# BaseMachine_Exio_Board.net
KiCad netlist of a schematic drawn in EAGLE
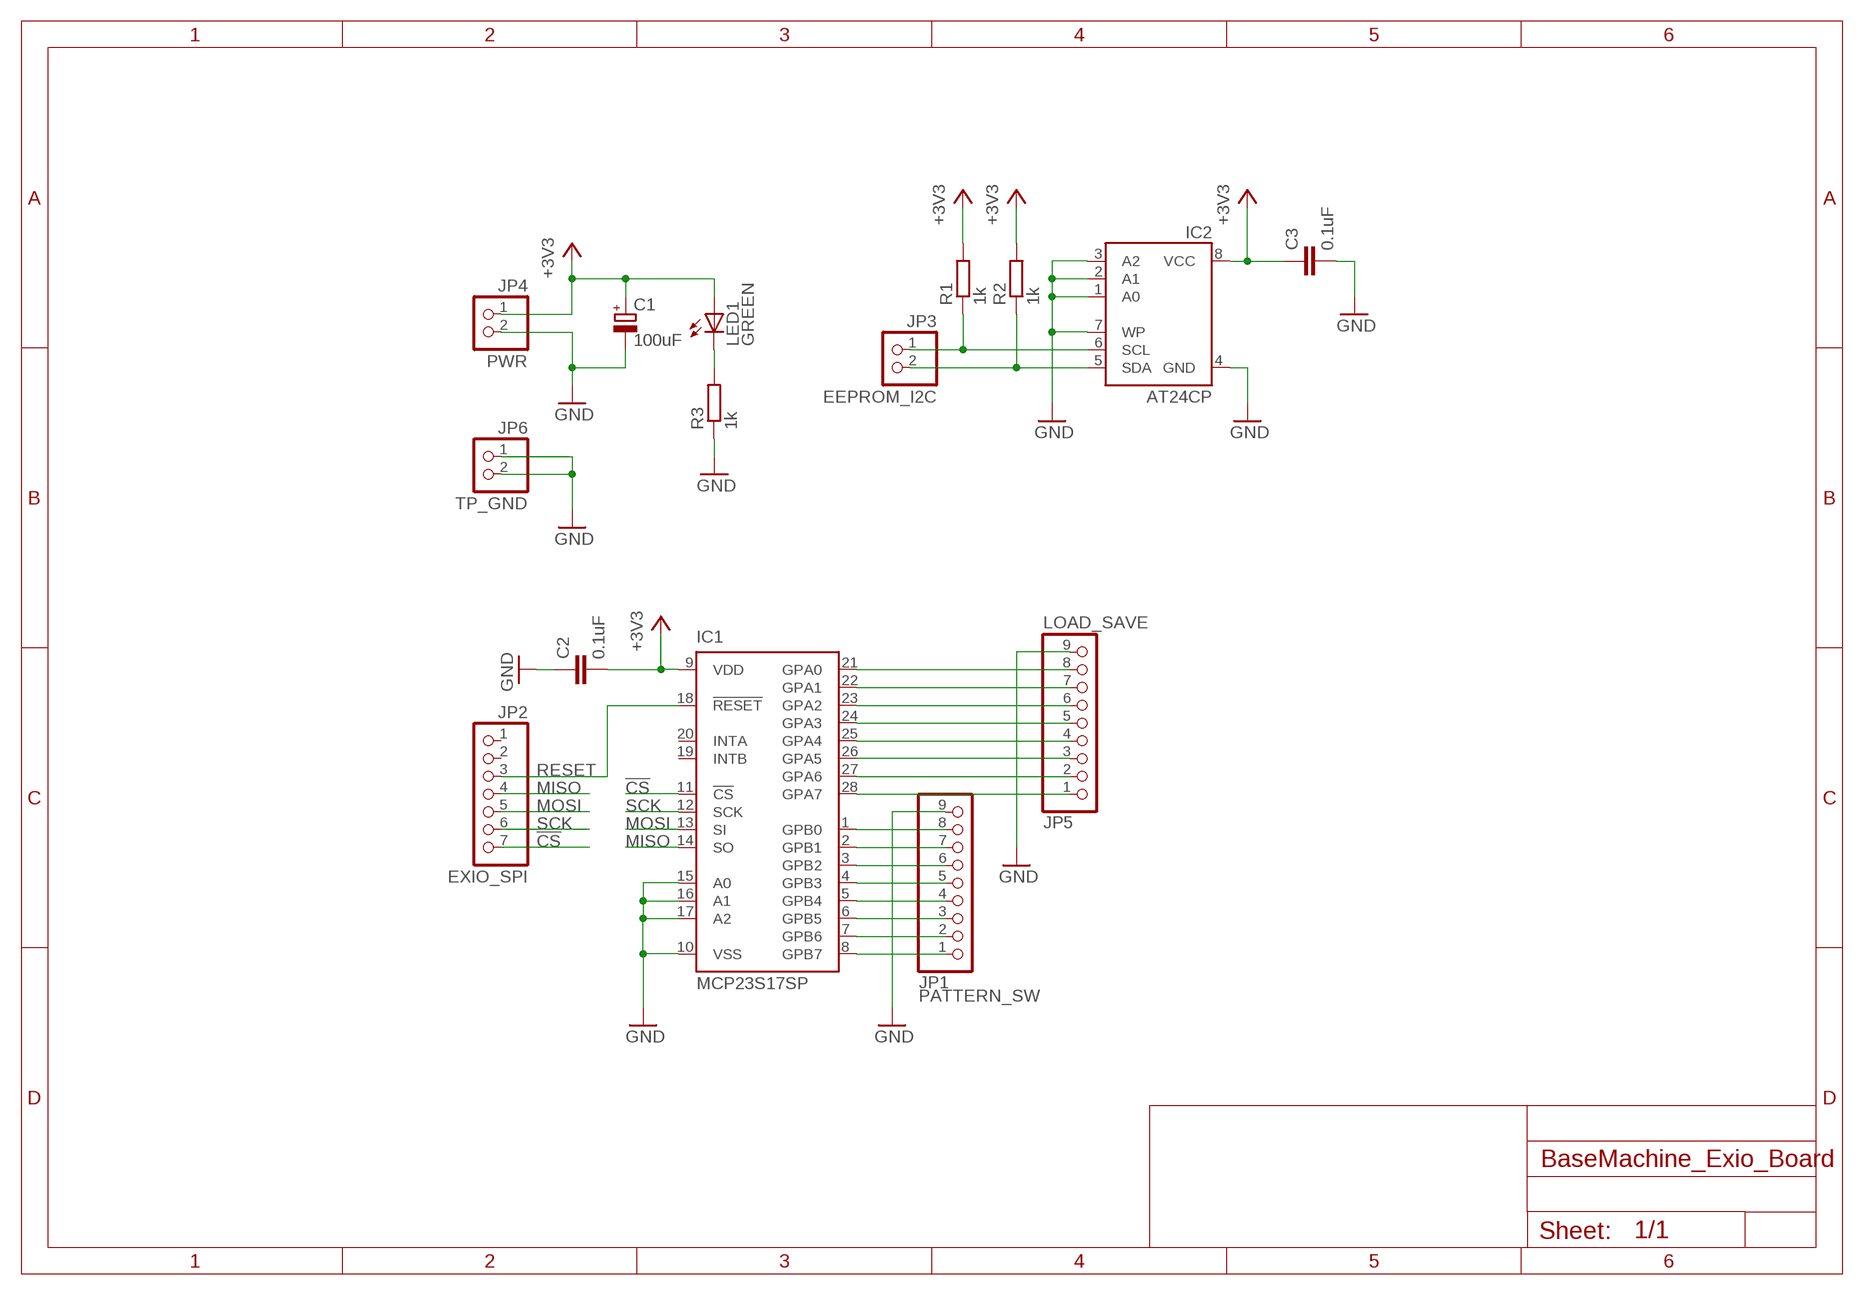
[diagram p0: schematic, sheet 1]

(export (version "E")
  (design (tool "Eeschema 10.0.6"))
  (components
    (comp (ref "C1")
      (value "100uF")
      (footprint "eagle-import:SANYO-OSCON_C6")
      (libsource (lib "eagle-import") (part "CPOL-EUSANYO_C6"))
    )
    (comp (ref "C2")
      (value "0.1uF")
      (footprint "eagle-import:C025-024X044")
      (libsource (lib "eagle-import") (part "C-EU025-024X044"))
    )
    (comp (ref "C3")
      (value "0.1uF")
      (footprint "eagle-import:C025-024X044")
      (libsource (lib "eagle-import") (part "C-EU025-024X044"))
    )
    (comp (ref "IC1")
      (value "MCP23S17SP")
      (footprint "eagle-import:DIL28-3")
      (fields (field (name "MF") "MICROCHIP") (field (name "MPN") "MCP23S17-E/SP"))
      (libsource (lib "eagle-import") (part "MCP23S17SP"))
    )
    (comp (ref "IC2")
      (value "AT24CP")
      (footprint "eagle-import:DIL08")
      (fields (field (name "MPN") "AT24C1024BW-SH-B"))
      (libsource (lib "eagle-import") (part "AT24CP"))
    )
    (comp (ref "JP1")
      (value "PATTERN_SW")
      (footprint "eagle-import:1X09_90")
      (libsource (lib "eagle-import") (part "PINHD-1X9/90"))
    )
    (comp (ref "JP2")
      (value "EXIO_SPI")
      (footprint "eagle-import:1X07_90")
      (libsource (lib "eagle-import") (part "PINHD-1X7/90"))
    )
    (comp (ref "JP3")
      (value "EEPROM_I2C")
      (footprint "eagle-import:1X02_90")
      (libsource (lib "eagle-import") (part "PINHD-1X2/90"))
    )
    (comp (ref "JP4")
      (value "PWR")
      (footprint "eagle-import:1X02_90")
      (libsource (lib "eagle-import") (part "PINHD-1X2/90"))
    )
    (comp (ref "JP5")
      (value "LOAD_SAVE")
      (footprint "eagle-import:1X09_90")
      (libsource (lib "eagle-import") (part "PINHD-1X9/90"))
    )
    (comp (ref "JP6")
      (value "TP_GND")
      (footprint "eagle-import:1X02")
      (libsource (lib "eagle-import") (part "PINHD-1X2"))
    )
    (comp (ref "LED1")
      (value "GREEN")
      (footprint "eagle-import:LED3MM")
      (libsource (lib "eagle-import") (part "LED3MM"))
    )
    (comp (ref "R1")
      (value "1k")
      (footprint "eagle-import:0207_7")
      (libsource (lib "eagle-import") (part "R-EU_0207/7"))
    )
    (comp (ref "R2")
      (value "1k")
      (footprint "eagle-import:0207_7")
      (libsource (lib "eagle-import") (part "R-EU_0207/7"))
    )
    (comp (ref "R3")
      (value "1k")
      (footprint "eagle-import:0207_7")
      (libsource (lib "eagle-import") (part "R-EU_0207/7"))
    )
  )
  (nets
    (net (code "1") (name "+3V3") (class "Default")
      (node (ref "C1") (pin "+") (pinfunction "+_+") (pintype "passive"))
      (node (ref "C2") (pin "2") (pinfunction "2_2") (pintype "passive"))
      (node (ref "C3") (pin "1") (pinfunction "1_1") (pintype "passive"))
      (node (ref "IC1") (pin "9") (pinfunction "VDD_9") (pintype "power_in"))
      (node (ref "IC2") (pin "8") (pinfunction "VCC_8") (pintype "power_in"))
      (node (ref "JP4") (pin "1") (pinfunction "1_1") (pintype "passive"))
      (node (ref "LED1") (pin "A") (pinfunction "A_A") (pintype "passive"))
      (node (ref "R1") (pin "2") (pinfunction "2_2") (pintype "passive"))
      (node (ref "R2") (pin "2") (pinfunction "2_2") (pintype "passive"))
    )
    (net (code "2") (name "/MISO") (class "Default")
      (node (ref "IC1") (pin "14") (pinfunction "SO_14") (pintype "output"))
      (node (ref "JP2") (pin "4") (pinfunction "4_4") (pintype "passive"))
    )
    (net (code "3") (name "/MOSI") (class "Default")
      (node (ref "IC1") (pin "13") (pinfunction "SI_13") (pintype "input"))
      (node (ref "JP2") (pin "5") (pinfunction "5_5") (pintype "passive"))
    )
    (net (code "4") (name "/RESET") (class "Default")
      (node (ref "IC1") (pin "18") (pinfunction "~{RESET}_18") (pintype "input"))
      (node (ref "JP2") (pin "3") (pinfunction "3_3") (pintype "passive"))
    )
    (net (code "5") (name "/SCK") (class "Default")
      (node (ref "IC1") (pin "12") (pinfunction "SCK_12") (pintype "input"))
      (node (ref "JP2") (pin "6") (pinfunction "6_6") (pintype "passive"))
    )
    (net (code "6") (name "/~{CS}") (class "Default")
      (node (ref "IC1") (pin "11") (pinfunction "~{CS}_11") (pintype "input"))
      (node (ref "JP2") (pin "7") (pinfunction "7_7") (pintype "passive"))
    )
    (net (code "7") (name "GND") (class "Default")
      (node (ref "C1") (pin "-") (pinfunction "-_-") (pintype "passive"))
      (node (ref "C2") (pin "1") (pinfunction "1_1") (pintype "passive"))
      (node (ref "C3") (pin "2") (pinfunction "2_2") (pintype "passive"))
      (node (ref "IC1") (pin "10") (pinfunction "VSS_10") (pintype "power_in"))
      (node (ref "IC1") (pin "15") (pinfunction "A0_15") (pintype "input"))
      (node (ref "IC1") (pin "16") (pinfunction "A1_16") (pintype "input"))
      (node (ref "IC1") (pin "17") (pinfunction "A2_17") (pintype "input"))
      (node (ref "IC2") (pin "1") (pinfunction "A0_1") (pintype "input"))
      (node (ref "IC2") (pin "2") (pinfunction "A1_2") (pintype "input"))
      (node (ref "IC2") (pin "3") (pinfunction "A2_3") (pintype "input"))
      (node (ref "IC2") (pin "4") (pinfunction "GND_4") (pintype "power_in"))
      (node (ref "IC2") (pin "7") (pinfunction "WP_7") (pintype "input"))
      (node (ref "JP1") (pin "9") (pinfunction "9_9") (pintype "passive"))
      (node (ref "JP4") (pin "2") (pinfunction "2_2") (pintype "passive"))
      (node (ref "JP5") (pin "9") (pinfunction "9_9") (pintype "passive"))
      (node (ref "JP6") (pin "1") (pinfunction "1_1") (pintype "passive"))
      (node (ref "JP6") (pin "2") (pinfunction "2_2") (pintype "passive"))
      (node (ref "R3") (pin "1") (pinfunction "1_1") (pintype "passive"))
    )
    (net (code "8") (name "Net-(IC1-GPA0)") (class "Default")
      (node (ref "IC1") (pin "21") (pinfunction "GPA0_21") (pintype "bidirectional"))
      (node (ref "JP5") (pin "8") (pinfunction "8_8") (pintype "passive"))
    )
    (net (code "9") (name "Net-(IC1-GPA1)") (class "Default")
      (node (ref "IC1") (pin "22") (pinfunction "GPA1_22") (pintype "bidirectional"))
      (node (ref "JP5") (pin "7") (pinfunction "7_7") (pintype "passive"))
    )
    (net (code "10") (name "Net-(IC1-GPA2)") (class "Default")
      (node (ref "IC1") (pin "23") (pinfunction "GPA2_23") (pintype "bidirectional"))
      (node (ref "JP5") (pin "6") (pinfunction "6_6") (pintype "passive"))
    )
    (net (code "11") (name "Net-(IC1-GPA3)") (class "Default")
      (node (ref "IC1") (pin "24") (pinfunction "GPA3_24") (pintype "bidirectional"))
      (node (ref "JP5") (pin "5") (pinfunction "5_5") (pintype "passive"))
    )
    (net (code "12") (name "Net-(IC1-GPA4)") (class "Default")
      (node (ref "IC1") (pin "25") (pinfunction "GPA4_25") (pintype "bidirectional"))
      (node (ref "JP5") (pin "4") (pinfunction "4_4") (pintype "passive"))
    )
    (net (code "13") (name "Net-(IC1-GPA5)") (class "Default")
      (node (ref "IC1") (pin "26") (pinfunction "GPA5_26") (pintype "bidirectional"))
      (node (ref "JP5") (pin "3") (pinfunction "3_3") (pintype "passive"))
    )
    (net (code "14") (name "Net-(IC1-GPA6)") (class "Default")
      (node (ref "IC1") (pin "27") (pinfunction "GPA6_27") (pintype "bidirectional"))
      (node (ref "JP5") (pin "2") (pinfunction "2_2") (pintype "passive"))
    )
    (net (code "15") (name "Net-(IC1-GPA7)") (class "Default")
      (node (ref "IC1") (pin "28") (pinfunction "GPA7_28") (pintype "bidirectional"))
      (node (ref "JP5") (pin "1") (pinfunction "1_1") (pintype "passive"))
    )
    (net (code "16") (name "Net-(IC1-GPB0)") (class "Default")
      (node (ref "IC1") (pin "1") (pinfunction "GPB0_1") (pintype "bidirectional"))
      (node (ref "JP1") (pin "8") (pinfunction "8_8") (pintype "passive"))
    )
    (net (code "17") (name "Net-(IC1-GPB1)") (class "Default")
      (node (ref "IC1") (pin "2") (pinfunction "GPB1_2") (pintype "bidirectional"))
      (node (ref "JP1") (pin "7") (pinfunction "7_7") (pintype "passive"))
    )
    (net (code "18") (name "Net-(IC1-GPB2)") (class "Default")
      (node (ref "IC1") (pin "3") (pinfunction "GPB2_3") (pintype "bidirectional"))
      (node (ref "JP1") (pin "6") (pinfunction "6_6") (pintype "passive"))
    )
    (net (code "19") (name "Net-(IC1-GPB3)") (class "Default")
      (node (ref "IC1") (pin "4") (pinfunction "GPB3_4") (pintype "bidirectional"))
      (node (ref "JP1") (pin "5") (pinfunction "5_5") (pintype "passive"))
    )
    (net (code "20") (name "Net-(IC1-GPB4)") (class "Default")
      (node (ref "IC1") (pin "5") (pinfunction "GPB4_5") (pintype "bidirectional"))
      (node (ref "JP1") (pin "4") (pinfunction "4_4") (pintype "passive"))
    )
    (net (code "21") (name "Net-(IC1-GPB5)") (class "Default")
      (node (ref "IC1") (pin "6") (pinfunction "GPB5_6") (pintype "bidirectional"))
      (node (ref "JP1") (pin "3") (pinfunction "3_3") (pintype "passive"))
    )
    (net (code "22") (name "Net-(IC1-GPB6)") (class "Default")
      (node (ref "IC1") (pin "7") (pinfunction "GPB6_7") (pintype "bidirectional"))
      (node (ref "JP1") (pin "2") (pinfunction "2_2") (pintype "passive"))
    )
    (net (code "23") (name "Net-(IC1-GPB7)") (class "Default")
      (node (ref "IC1") (pin "8") (pinfunction "GPB7_8") (pintype "bidirectional"))
      (node (ref "JP1") (pin "1") (pinfunction "1_1") (pintype "passive"))
    )
    (net (code "24") (name "Net-(IC2-SCL)") (class "Default")
      (node (ref "IC2") (pin "6") (pinfunction "SCL_6") (pintype "bidirectional"))
      (node (ref "JP3") (pin "1") (pinfunction "1_1") (pintype "passive"))
      (node (ref "R1") (pin "1") (pinfunction "1_1") (pintype "passive"))
    )
    (net (code "25") (name "Net-(IC2-SDA)") (class "Default")
      (node (ref "IC2") (pin "5") (pinfunction "SDA_5") (pintype "bidirectional"))
      (node (ref "JP3") (pin "2") (pinfunction "2_2") (pintype "passive"))
      (node (ref "R2") (pin "1") (pinfunction "1_1") (pintype "passive"))
    )
    (net (code "26") (name "Net-(LED1-C)") (class "Default")
      (node (ref "LED1") (pin "K") (pinfunction "C_K") (pintype "passive"))
      (node (ref "R3") (pin "2") (pinfunction "2_2") (pintype "passive"))
    )
    (net (code "27") (name "unconnected-(IC1-INTA-Pad20)") (class "Default")
      (node (ref "IC1") (pin "20") (pinfunction "INTA_20") (pintype "output"))
    )
    (net (code "28") (name "unconnected-(IC1-INTB-Pad19)") (class "Default")
      (node (ref "IC1") (pin "19") (pinfunction "INTB_19") (pintype "output"))
    )
    (net (code "29") (name "unconnected-(JP2-Pad1)") (class "Default")
      (node (ref "JP2") (pin "1") (pinfunction "1_1") (pintype "passive"))
    )
    (net (code "30") (name "unconnected-(JP2-Pad2)") (class "Default")
      (node (ref "JP2") (pin "2") (pinfunction "2_2") (pintype "passive"))
    )
  )
)
